# Force_sensor_PCB_Easy_EDA_Proffesional_p.net
KiCad netlist of a schematic drawn in EasyEDA Pro
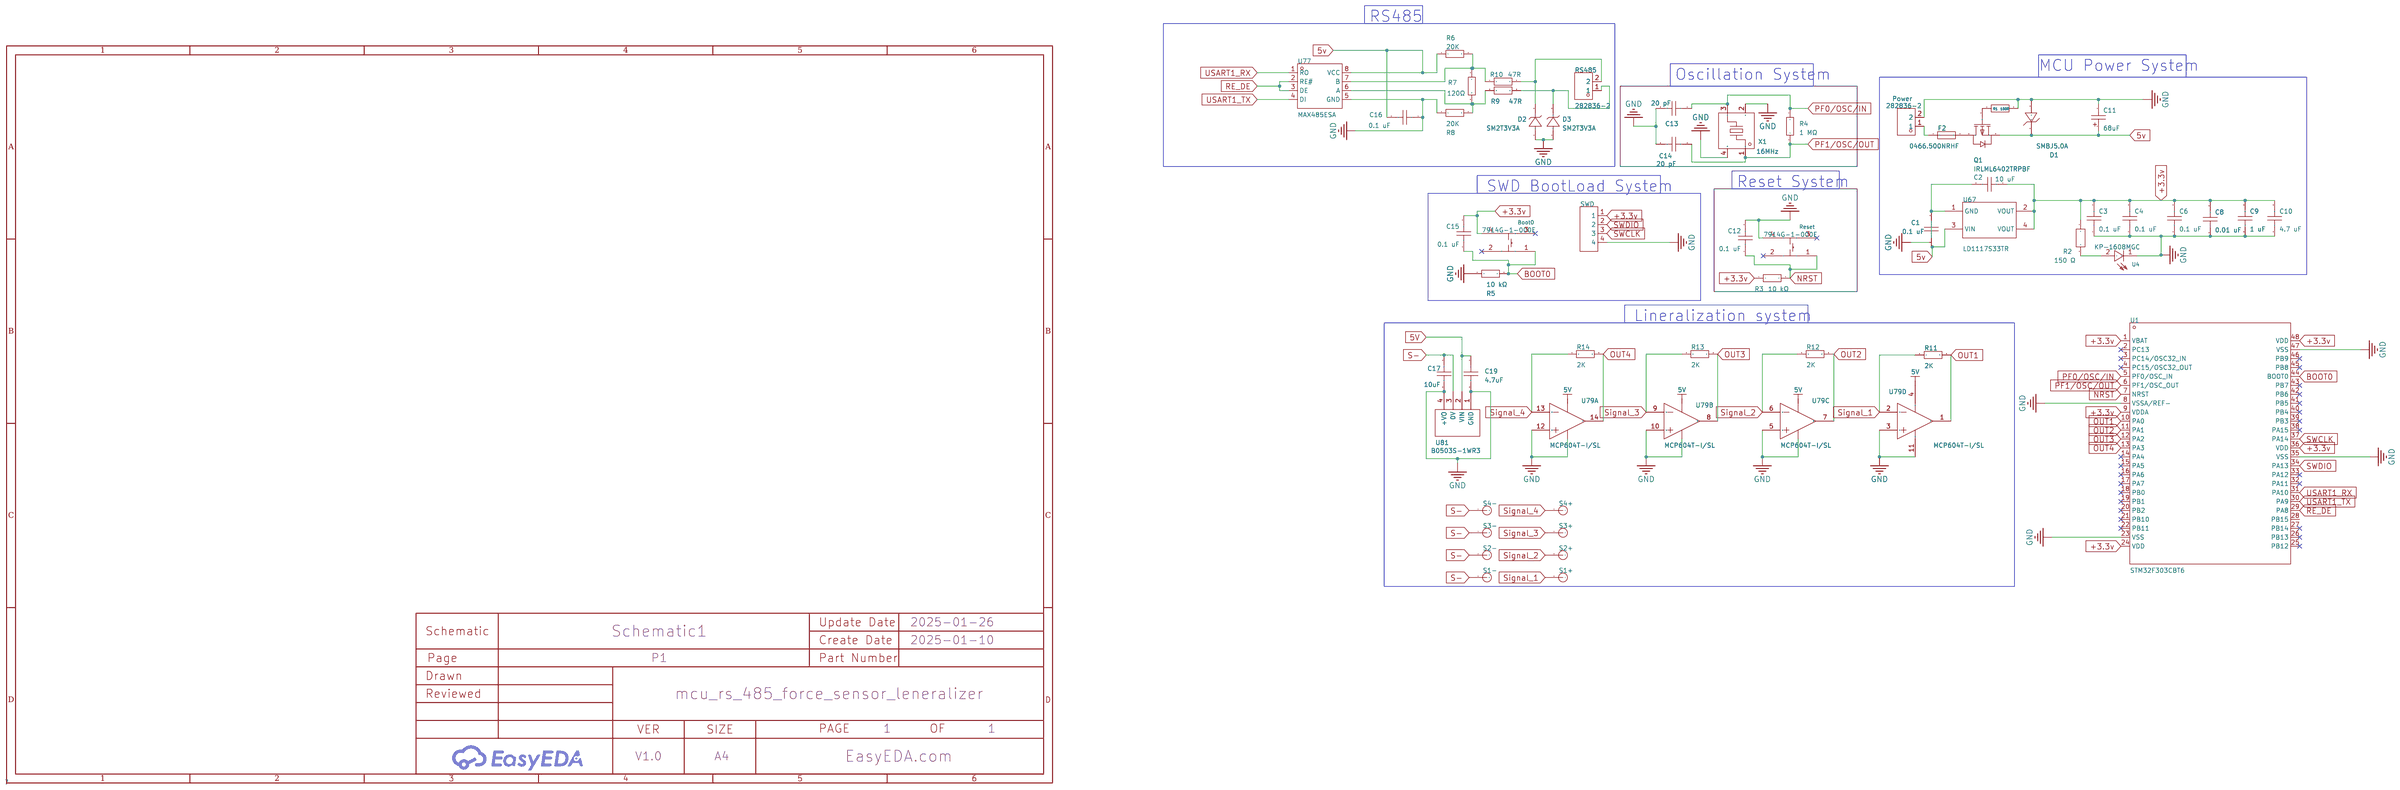
[diagram p0: schematic sheet]

(export (version "E")
  (design (tool "Eeschema 10.0.6"))
  (components
    (comp (ref "Boot0")
      (value "7914G-1-000E")
      (footprint "easyedapro:KEY-SMD_4P-L5.0-W5.0-P2.54-LS5.5-BL")
      (fields (field (name "Manufacturer") "BOURNS"))
      (libsource (lib "easyedapro") (part "7914G-1-000E"))
    )
    (comp (ref "C1")
      (value "0.1 uF")
      (footprint "easyedapro:C0201")
      (libsource (lib "easyedapro") (part "CAP"))
    )
    (comp (ref "C2")
      (value "10 uF")
      (footprint "easyedapro:C0201")
      (libsource (lib "easyedapro") (part "CAP"))
    )
    (comp (ref "C3")
      (value "0.1 uF")
      (footprint "easyedapro:C0201")
      (libsource (lib "easyedapro") (part "CAP"))
    )
    (comp (ref "C4")
      (value "0.1 uF")
      (footprint "easyedapro:C0201")
      (libsource (lib "easyedapro") (part "CAP"))
    )
    (comp (ref "C6")
      (value "0.1 uF")
      (footprint "easyedapro:C0201")
      (libsource (lib "easyedapro") (part "CAP"))
    )
    (comp (ref "C8")
      (value "0.01 uF")
      (footprint "easyedapro:C0201")
      (libsource (lib "easyedapro") (part "CAP"))
    )
    (comp (ref "C9")
      (value "1 uF")
      (footprint "easyedapro:C0201")
      (libsource (lib "easyedapro") (part "CAP"))
    )
    (comp (ref "C10")
      (value "4.7 uF")
      (footprint "easyedapro:C0201")
      (libsource (lib "easyedapro") (part "CAP"))
    )
    (comp (ref "C11")
      (value "68uF")
      (footprint "easyedapro:CASE-B_3528")
      (fields
        (field (name "Manufacturer Part") "TLJB227M006R0500")
        (field (name "Manufacturer") "Kyocera AVX")
      )
      (libsource (lib "easyedapro") (part "TLJB227M006R0500"))
    )
    (comp (ref "C12")
      (value "0.1 uF")
      (footprint "easyedapro:C0201")
      (libsource (lib "easyedapro") (part "CAP"))
    )
    (comp (ref "C13")
      (value "20 pF")
      (footprint "easyedapro:C0201")
      (libsource (lib "easyedapro") (part "CAP"))
    )
    (comp (ref "C14")
      (value "20 pF")
      (footprint "easyedapro:C0201")
      (libsource (lib "easyedapro") (part "CAP"))
    )
    (comp (ref "C15")
      (value "0.1 uF")
      (footprint "easyedapro:C0201")
      (libsource (lib "easyedapro") (part "CAP"))
    )
    (comp (ref "C16")
      (value "0.1 uF")
      (footprint "easyedapro:C0201")
      (libsource (lib "easyedapro") (part "CAP"))
    )
    (comp (ref "C17")
      (value "10uF")
      (footprint "easyedapro:C0201")
      (libsource (lib "easyedapro") (part "CAP"))
    )
    (comp (ref "C19")
      (value "4.7uF")
      (footprint "easyedapro:C0201")
      (libsource (lib "easyedapro") (part "CAP"))
    )
    (comp (ref "D1")
      (value "SMBJ5.0A")
      (footprint "easyedapro:SMB_L4.3-W3.6-LS5.4-RD")
      (fields (field (name "Manufacturer") "SEMBO(深波)"))
      (libsource (lib "easyedapro") (part "SMBJ5.0A_C782420"))
    )
    (comp (ref "D2")
      (value "SM2T3V3A")
      (footprint "easyedapro:DO-216AA_L1.9-W1.9-LS3.8-FD")
      (fields (field (name "Manufacturer") "ST(意法半导体)"))
      (libsource (lib "easyedapro") (part "SM2T3V3A"))
    )
    (comp (ref "D3")
      (value "SM2T3V3A")
      (footprint "easyedapro:DO-216AA_L1.9-W1.9-LS3.8-FD")
      (fields (field (name "Manufacturer") "ST(意法半导体)"))
      (libsource (lib "easyedapro") (part "SM2T3V3A"))
    )
    (comp (ref "F2")
      (value "0466.500NRHF")
      (footprint "easyedapro:F1206")
      (fields (field (name "Manufacturer") "Littelfuse(美国力特)"))
      (libsource (lib "easyedapro") (part "0466.500NRHF"))
    )
    (comp (ref "Power")
      (value "282836-2")
      (footprint "easyedapro:CONN-TH_2P-P5.00_282836-2")
      (fields (field (name "Manufacturer") "TE Connectivity(泰科电子)"))
      (libsource (lib "easyedapro") (part "282836-2"))
    )
    (comp (ref "Q1")
      (value "IRLML6402TRPBF")
      (footprint "easyedapro:SOT-23-3_L2.9-W1.6-P1.90-LS2.8-BR")
      (fields (field (name "Manufacturer") "Infineon(英飞凌)"))
      (libsource (lib "easyedapro") (part "IRLML6402TRPBF"))
    )
    (comp (ref "R1")
      (value "100R")
      (footprint "easyedapro:R0603")
      (libsource (lib "easyedapro") (part "Res"))
    )
    (comp (ref "R2")
      (value "150 Ω")
      (footprint "easyedapro:R0805")
      (fields (field (name "Manufacturer Part") "ERJ6ENF2053V") (field (name "Manufacturer") "PANASONIC(松下)"))
      (libsource (lib "easyedapro") (part "ERJ6ENF2053V"))
    )
    (comp (ref "R3")
      (value "10 kΩ")
      (footprint "easyedapro:R0603")
      (libsource (lib "easyedapro") (part "Res"))
    )
    (comp (ref "R4")
      (value "1 MΩ")
      (footprint "easyedapro:R0603")
      (libsource (lib "easyedapro") (part "Res"))
    )
    (comp (ref "R5")
      (value "10 kΩ")
      (footprint "easyedapro:R0603")
      (libsource (lib "easyedapro") (part "Res"))
    )
    (comp (ref "R6") (value "20K") (footprint "easyedapro:R0603") (libsource (lib "easyedapro") (part "Res")))
    (comp (ref "R7")
      (value "120Ω")
      (footprint "easyedapro:R1206")
      (fields
        (field (name "Manufacturer Part") "1206W4J0121T5E")
        (field (name "Manufacturer") "UNI-ROYAL(厚声)")
      )
      (libsource (lib "easyedapro") (part "1206W4J0121T5E"))
    )
    (comp (ref "R8") (value "20K") (footprint "easyedapro:R0603") (libsource (lib "easyedapro") (part "Res")))
    (comp (ref "R9") (value "47R") (footprint "easyedapro:R0603") (libsource (lib "easyedapro") (part "Res")))
    (comp (ref "R10")
      (value "47R")
      (footprint "easyedapro:R0603")
      (libsource (lib "easyedapro") (part "Res"))
    )
    (comp (ref "R11") (value "2K") (footprint "easyedapro:R0603") (libsource (lib "easyedapro") (part "Res")))
    (comp (ref "R12") (value "2K") (footprint "easyedapro:R0603") (libsource (lib "easyedapro") (part "Res")))
    (comp (ref "R13") (value "2K") (footprint "easyedapro:R0603") (libsource (lib "easyedapro") (part "Res")))
    (comp (ref "R14") (value "2K") (footprint "easyedapro:R0603") (libsource (lib "easyedapro") (part "Res")))
    (comp (ref "Reset")
      (value "7914G-1-000E")
      (footprint "easyedapro:KEY-SMD_4P-L5.0-W5.0-P2.54-LS5.5-BL")
      (fields (field (name "Manufacturer") "BOURNS"))
      (libsource (lib "easyedapro") (part "7914G-1-000E"))
    )
    (comp (ref "RS485")
      (value "282836-2")
      (footprint "easyedapro:CONN-TH_2P-P5.00_282836-2")
      (fields (field (name "Manufacturer") "TE Connectivity(泰科电子)"))
      (libsource (lib "easyedapro") (part "282836-2"))
    )
    (comp (ref "S1+")
      (value "~")
      (footprint "easyedapro:robust_pin")
      (libsource (lib "easyedapro") (part "robust_pin"))
    )
    (comp (ref "S1-")
      (value "~")
      (footprint "easyedapro:robust_pin")
      (libsource (lib "easyedapro") (part "robust_pin"))
    )
    (comp (ref "S2+")
      (value "~")
      (footprint "easyedapro:robust_pin")
      (libsource (lib "easyedapro") (part "robust_pin"))
    )
    (comp (ref "S2-")
      (value "~")
      (footprint "easyedapro:robust_pin")
      (libsource (lib "easyedapro") (part "robust_pin"))
    )
    (comp (ref "S3+")
      (value "~")
      (footprint "easyedapro:robust_pin")
      (libsource (lib "easyedapro") (part "robust_pin"))
    )
    (comp (ref "S3-")
      (value "~")
      (footprint "easyedapro:robust_pin")
      (libsource (lib "easyedapro") (part "robust_pin"))
    )
    (comp (ref "S4+")
      (value "~")
      (footprint "easyedapro:robust_pin")
      (libsource (lib "easyedapro") (part "robust_pin"))
    )
    (comp (ref "S4-")
      (value "~")
      (footprint "easyedapro:robust_pin")
      (libsource (lib "easyedapro") (part "robust_pin"))
    )
    (comp (ref "SWD")
      (value "~")
      (footprint "easyedapro:HDR-TH_4P-P2.54-V-M")
      (libsource (lib "easyedapro") (part "PZ254V-11-04P"))
    )
    (comp (ref "U1")
      (value "STM32F303CBT6")
      (footprint "easyedapro:LQFP-48_L7.0-W7.0-P0.50-LS9.0-BL")
      (fields (field (name "Manufacturer") "ST(意法半导体)"))
      (libsource (lib "easyedapro") (part "STM32F303CBT6"))
    )
    (comp (ref "U4")
      (value "KP-1608MGC")
      (footprint "easyedapro:LED0603-RD_GREEN")
      (fields (field (name "Manufacturer") "Kingbright"))
      (libsource (lib "easyedapro") (part "KP-1608MGC"))
    )
    (comp (ref "U67")
      (value "LD1117S33TR")
      (footprint "easyedapro:SOT-223_L6.5-W3.5-P2.30-LS7.0-BR")
      (fields (field (name "Manufacturer") "ST(意法半导体)"))
      (libsource (lib "easyedapro") (part "LD1117S33TR"))
    )
    (comp (ref "U77")
      (value "MAX485ESA")
      (footprint "easyedapro:SOIC-8_L4.9-W3.9-P1.27-LS6.0-BL")
      (fields (field (name "Manufacturer") "TWGMC(台湾迪嘉)"))
      (libsource (lib "easyedapro") (part "MAX485ESA_C5279041"))
    )
    (comp (ref "U79")
      (value "MCP604T-I/SL")
      (footprint "easyedapro:SOIC-14_L8.7-W3.9-P1.27-LS6.0-BL")
      (fields (field (name "Manufacturer") "MICROCHIP(美国微芯)"))
      (libsource (lib "easyedapro") (part "MCP604T-I/SL"))
    )
    (comp (ref "U81")
      (value "B0503S-1WR3")
      (footprint "easyedapro:PWRM-TH_B0503S-1WR2")
      (fields (field (name "Manufacturer") "DEXU(德旭电子)"))
      (libsource (lib "easyedapro") (part "B0503S-1WR3_C909801"))
    )
    (comp (ref "X1")
      (value "16MHz")
      (footprint "easyedapro:CRYSTAL-SMD_4P-L5.0-W3.2-BL")
      (fields
        (field (name "Manufacturer Part") "HY13MSMD50324POB1R10")
        (field (name "Manufacturer") "Huiyuan crystal(惠源晶工)")
      )
      (libsource (lib "easyedapro") (part "HY13MSMD50324POB1R10"))
    )
  )
  (nets
    (net (code "1") (name "+3.3v") (class "Default")
      (node (ref "Boot0") (pin "4") (pinfunction "4_4") (pintype "unspecified"))
      (node (ref "C10") (pin "2") (pinfunction "2_2") (pintype "input"))
      (node (ref "C15") (pin "2") (pinfunction "2_2") (pintype "input"))
      (node (ref "C2") (pin "1") (pinfunction "1_1") (pintype "input"))
      (node (ref "C3") (pin "2") (pinfunction "2_2") (pintype "input"))
      (node (ref "C4") (pin "2") (pinfunction "2_2") (pintype "input"))
      (node (ref "C6") (pin "2") (pinfunction "2_2") (pintype "input"))
      (node (ref "C8") (pin "2") (pinfunction "2_2") (pintype "input"))
      (node (ref "C9") (pin "2") (pinfunction "2_2") (pintype "input"))
      (node (ref "R2") (pin "1") (pinfunction "1_1") (pintype "unspecified"))
      (node (ref "R3") (pin "1") (pinfunction "1_1") (pintype "input"))
      (node (ref "SWD") (pin "1") (pinfunction "1_1") (pintype "unspecified"))
      (node (ref "U1") (pin "1") (pinfunction "VBAT_1") (pintype "unspecified"))
      (node (ref "U1") (pin "24") (pinfunction "VDD_24") (pintype "unspecified"))
      (node (ref "U1") (pin "36") (pinfunction "VDD_36") (pintype "unspecified"))
      (node (ref "U1") (pin "48") (pinfunction "VDD_48") (pintype "unspecified"))
      (node (ref "U1") (pin "9") (pinfunction "VDDA_9") (pintype "unspecified"))
      (node (ref "U67") (pin "2") (pinfunction "VOUT_2") (pintype "unspecified"))
      (node (ref "U67") (pin "4") (pinfunction "VOUT_4") (pintype "unspecified"))
    )
    (net (code "2") (name "5V") (class "Default")
      (node (ref "C19") (pin "1") (pinfunction "1_1") (pintype "input"))
      (node (ref "U79") (pin "4") (pinfunction "VDD_4") (pintype "unspecified"))
      (node (ref "U81") (pin "2") (pinfunction "VIN_2") (pintype "unspecified"))
    )
    (net (code "3") (name "5v") (class "Default")
      (node (ref "C1") (pin "1") (pinfunction "1_1") (pintype "input"))
      (node (ref "C11") (pin "1") (pinfunction "1_1") (pintype "input"))
      (node (ref "C16") (pin "2") (pinfunction "2_2") (pintype "input"))
      (node (ref "D1") (pin "1") (pinfunction "C_1") (pintype "unspecified"))
      (node (ref "Q1") (pin "2") (pinfunction "S_2") (pintype "unspecified"))
      (node (ref "R6") (pin "1") (pinfunction "1_1") (pintype "input"))
      (node (ref "U67") (pin "3") (pinfunction "VIN_3") (pintype "unspecified"))
      (node (ref "U77") (pin "8") (pinfunction "VCC_8") (pintype "unspecified"))
    )
    (net (code "4") (name "BOOT0") (class "Default")
      (node (ref "Boot0") (pin "1") (pinfunction "1_1") (pintype "unspecified"))
      (node (ref "C15") (pin "1") (pinfunction "1_1") (pintype "input"))
      (node (ref "R5") (pin "2") (pinfunction "2_2") (pintype "input"))
      (node (ref "U1") (pin "44") (pinfunction "BOOT0_44") (pintype "unspecified"))
    )
    (net (code "5") (name "GND") (class "Default")
      (node (ref "C1") (pin "2") (pinfunction "2_2") (pintype "input"))
      (node (ref "C10") (pin "1") (pinfunction "1_1") (pintype "input"))
      (node (ref "C11") (pin "2") (pinfunction "2_2") (pintype "input"))
      (node (ref "C12") (pin "2") (pinfunction "2_2") (pintype "input"))
      (node (ref "C13") (pin "2") (pinfunction "2_2") (pintype "input"))
      (node (ref "C14") (pin "2") (pinfunction "2_2") (pintype "input"))
      (node (ref "C16") (pin "1") (pinfunction "1_1") (pintype "input"))
      (node (ref "C17") (pin "2") (pinfunction "2_2") (pintype "input"))
      (node (ref "C19") (pin "2") (pinfunction "2_2") (pintype "input"))
      (node (ref "C2") (pin "2") (pinfunction "2_2") (pintype "input"))
      (node (ref "C3") (pin "1") (pinfunction "1_1") (pintype "input"))
      (node (ref "C4") (pin "1") (pinfunction "1_1") (pintype "input"))
      (node (ref "C6") (pin "1") (pinfunction "1_1") (pintype "input"))
      (node (ref "C8") (pin "1") (pinfunction "1_1") (pintype "input"))
      (node (ref "C9") (pin "1") (pinfunction "1_1") (pintype "input"))
      (node (ref "D1") (pin "2") (pinfunction "A_2") (pintype "unspecified"))
      (node (ref "D2") (pin "1") (pinfunction "A_1") (pintype "unspecified"))
      (node (ref "D3") (pin "1") (pinfunction "A_1") (pintype "unspecified"))
      (node (ref "Power") (pin "2") (pinfunction "2_2") (pintype "unspecified"))
      (node (ref "R1") (pin "2") (pinfunction "2_2") (pintype "input"))
      (node (ref "R5") (pin "1") (pinfunction "1_1") (pintype "input"))
      (node (ref "R8") (pin "1") (pinfunction "1_1") (pintype "input"))
      (node (ref "Reset") (pin "4") (pinfunction "4_4") (pintype "unspecified"))
      (node (ref "SWD") (pin "4") (pinfunction "4_4") (pintype "unspecified"))
      (node (ref "U1") (pin "23") (pinfunction "VSS_23") (pintype "unspecified"))
      (node (ref "U1") (pin "35") (pinfunction "VSS_35") (pintype "unspecified"))
      (node (ref "U1") (pin "47") (pinfunction "VSS_47") (pintype "unspecified"))
      (node (ref "U1") (pin "8") (pinfunction "VSSA/REF-_8") (pintype "unspecified"))
      (node (ref "U4") (pin "1") (pinfunction "C_1") (pintype "input"))
      (node (ref "U67") (pin "1") (pinfunction "GND_1") (pintype "unspecified"))
      (node (ref "U77") (pin "5") (pinfunction "GND_5") (pintype "unspecified"))
      (node (ref "U79") (pin "10") (pinfunction "VINC+_10") (pintype "unspecified"))
      (node (ref "U79") (pin "11") (pinfunction "VSS_11") (pintype "unspecified"))
      (node (ref "U79") (pin "12") (pinfunction "VIND+_12") (pintype "unspecified"))
      (node (ref "U79") (pin "3") (pinfunction "VINA+_3") (pintype "unspecified"))
      (node (ref "U79") (pin "5") (pinfunction "VINB+_5") (pintype "unspecified"))
      (node (ref "U81") (pin "1") (pinfunction "GND_1") (pintype "unspecified"))
      (node (ref "U81") (pin "4") (pinfunction "+VO_4") (pintype "unspecified"))
      (node (ref "X1") (pin "2") (pinfunction "GND_2") (pintype "input"))
      (node (ref "X1") (pin "4") (pinfunction "GND_4") (pintype "input"))
    )
    (net (code "6") (name "NRST") (class "Default")
      (node (ref "C12") (pin "1") (pinfunction "1_1") (pintype "input"))
      (node (ref "R3") (pin "2") (pinfunction "2_2") (pintype "input"))
      (node (ref "Reset") (pin "1") (pinfunction "1_1") (pintype "unspecified"))
      (node (ref "U1") (pin "7") (pinfunction "NRST_7") (pintype "unspecified"))
    )
    (net (code "7") (name "Net-(D2-K)") (class "Default")
      (node (ref "D2") (pin "2") (pinfunction "K_2") (pintype "unspecified"))
      (node (ref "R10") (pin "2") (pinfunction "2_2") (pintype "input"))
      (node (ref "RS485") (pin "2") (pinfunction "2_2") (pintype "unspecified"))
    )
    (net (code "8") (name "Net-(D3-K)") (class "Default")
      (node (ref "D3") (pin "2") (pinfunction "K_2") (pintype "unspecified"))
      (node (ref "R9") (pin "2") (pinfunction "2_2") (pintype "input"))
      (node (ref "RS485") (pin "1") (pinfunction "1_1") (pintype "unspecified"))
    )
    (net (code "9") (name "Net-(F2-Pad1)") (class "Default")
      (node (ref "F2") (pin "1") (pinfunction "1_1") (pintype "unspecified"))
      (node (ref "Power") (pin "1") (pinfunction "1_1") (pintype "unspecified"))
    )
    (net (code "10") (name "Net-(Q1-D)") (class "Default")
      (node (ref "F2") (pin "2") (pinfunction "2_2") (pintype "unspecified"))
      (node (ref "Q1") (pin "3") (pinfunction "D_3") (pintype "unspecified"))
    )
    (net (code "11") (name "Net-(Q1-G)") (class "Default")
      (node (ref "Q1") (pin "1") (pinfunction "G_1") (pintype "unspecified"))
      (node (ref "R1") (pin "1") (pinfunction "1_1") (pintype "input"))
    )
    (net (code "12") (name "Net-(U4-A)") (class "Default")
      (node (ref "R2") (pin "2") (pinfunction "2_2") (pintype "unspecified"))
      (node (ref "U4") (pin "2") (pinfunction "A_2") (pintype "input"))
    )
    (net (code "13") (name "Net-(U77-A)") (class "Default")
      (node (ref "R7") (pin "2") (pinfunction "2_2") (pintype "input"))
      (node (ref "R8") (pin "2") (pinfunction "2_2") (pintype "input"))
      (node (ref "R9") (pin "1") (pinfunction "1_1") (pintype "input"))
      (node (ref "U77") (pin "6") (pinfunction "A_6") (pintype "unspecified"))
    )
    (net (code "14") (name "Net-(U77-B)") (class "Default")
      (node (ref "R10") (pin "1") (pinfunction "1_1") (pintype "input"))
      (node (ref "R6") (pin "2") (pinfunction "2_2") (pintype "input"))
      (node (ref "R7") (pin "1") (pinfunction "1_1") (pintype "input"))
      (node (ref "U77") (pin "7") (pinfunction "B_7") (pintype "unspecified"))
    )
    (net (code "15") (name "OUT1") (class "Default")
      (node (ref "R11") (pin "2") (pinfunction "2_2") (pintype "input"))
      (node (ref "U1") (pin "10") (pinfunction "PA0_10") (pintype "unspecified"))
      (node (ref "U79") (pin "1") (pinfunction "VOUTA_1") (pintype "output"))
    )
    (net (code "16") (name "OUT2") (class "Default")
      (node (ref "R12") (pin "2") (pinfunction "2_2") (pintype "input"))
      (node (ref "U1") (pin "11") (pinfunction "PA1_11") (pintype "unspecified"))
      (node (ref "U79") (pin "7") (pinfunction "VOUTB_7") (pintype "output"))
    )
    (net (code "17") (name "OUT3") (class "Default")
      (node (ref "R13") (pin "2") (pinfunction "2_2") (pintype "input"))
      (node (ref "U1") (pin "12") (pinfunction "PA2_12") (pintype "unspecified"))
      (node (ref "U79") (pin "8") (pinfunction "VOUTC_8") (pintype "output"))
    )
    (net (code "18") (name "OUT4") (class "Default")
      (node (ref "R14") (pin "2") (pinfunction "2_2") (pintype "input"))
      (node (ref "U1") (pin "13") (pinfunction "PA3_13") (pintype "unspecified"))
      (node (ref "U79") (pin "14") (pinfunction "VOUTD_14") (pintype "output"))
    )
    (net (code "19") (name "PF0{slash}OSC{slash}IN") (class "Default")
      (node (ref "C13") (pin "1") (pinfunction "1_1") (pintype "input"))
      (node (ref "R4") (pin "1") (pinfunction "1_1") (pintype "input"))
      (node (ref "U1") (pin "5") (pinfunction "PF0/OSC_IN_5") (pintype "unspecified"))
      (node (ref "X1") (pin "3") (pinfunction "3_3") (pintype "input"))
    )
    (net (code "20") (name "PF1{slash}OSC{slash}OUT") (class "Default")
      (node (ref "C14") (pin "1") (pinfunction "1_1") (pintype "input"))
      (node (ref "R4") (pin "2") (pinfunction "2_2") (pintype "input"))
      (node (ref "U1") (pin "6") (pinfunction "PF1/OSC_OUT_6") (pintype "unspecified"))
      (node (ref "X1") (pin "1") (pinfunction "1_1") (pintype "input"))
    )
    (net (code "21") (name "RE_DE") (class "Default")
      (node (ref "U1") (pin "29") (pinfunction "PA8_29") (pintype "unspecified"))
      (node (ref "U77") (pin "2") (pinfunction "RE#_2") (pintype "unspecified"))
      (node (ref "U77") (pin "3") (pinfunction "DE_3") (pintype "unspecified"))
    )
    (net (code "22") (name "S-") (class "Default")
      (node (ref "C17") (pin "1") (pinfunction "1_1") (pintype "input"))
      (node (ref "S1-") (pin "1") (pinfunction "1_1") (pintype "input"))
      (node (ref "S2-") (pin "1") (pinfunction "1_1") (pintype "input"))
      (node (ref "S3-") (pin "1") (pinfunction "1_1") (pintype "input"))
      (node (ref "S4-") (pin "1") (pinfunction "1_1") (pintype "input"))
      (node (ref "U81") (pin "3") (pinfunction "0V_3") (pintype "unspecified"))
    )
    (net (code "23") (name "SWCLK") (class "Default")
      (node (ref "SWD") (pin "3") (pinfunction "3_3") (pintype "unspecified"))
      (node (ref "U1") (pin "37") (pinfunction "PA14_37") (pintype "unspecified"))
    )
    (net (code "24") (name "SWDIO") (class "Default")
      (node (ref "SWD") (pin "2") (pinfunction "2_2") (pintype "unspecified"))
      (node (ref "U1") (pin "34") (pinfunction "PA13_34") (pintype "unspecified"))
    )
    (net (code "25") (name "Signal_1") (class "Default")
      (node (ref "R11") (pin "1") (pinfunction "1_1") (pintype "input"))
      (node (ref "S1+") (pin "1") (pinfunction "1_1") (pintype "input"))
      (node (ref "U79") (pin "2") (pinfunction "VINA-_2") (pintype "unspecified"))
    )
    (net (code "26") (name "Signal_2") (class "Default")
      (node (ref "R12") (pin "1") (pinfunction "1_1") (pintype "input"))
      (node (ref "S2+") (pin "1") (pinfunction "1_1") (pintype "input"))
      (node (ref "U79") (pin "6") (pinfunction "VINB-_6") (pintype "unspecified"))
    )
    (net (code "27") (name "Signal_3") (class "Default")
      (node (ref "R13") (pin "1") (pinfunction "1_1") (pintype "input"))
      (node (ref "S3+") (pin "1") (pinfunction "1_1") (pintype "input"))
      (node (ref "U79") (pin "9") (pinfunction "VINC-_9") (pintype "unspecified"))
    )
    (net (code "28") (name "Signal_4") (class "Default")
      (node (ref "R14") (pin "1") (pinfunction "1_1") (pintype "input"))
      (node (ref "S4+") (pin "1") (pinfunction "1_1") (pintype "input"))
      (node (ref "U79") (pin "13") (pinfunction "VIND-_13") (pintype "unspecified"))
    )
    (net (code "29") (name "USART1_RX") (class "Default")
      (node (ref "U1") (pin "31") (pinfunction "PA10_31") (pintype "unspecified"))
      (node (ref "U77") (pin "1") (pinfunction "RO_1") (pintype "unspecified"))
    )
    (net (code "30") (name "USART1_TX") (class "Default")
      (node (ref "U1") (pin "30") (pinfunction "PA9_30") (pintype "unspecified"))
      (node (ref "U77") (pin "4") (pinfunction "DI_4") (pintype "unspecified"))
    )
    (net (code "31") (name "unconnected-(Boot0-Pad2)") (class "Default")
      (node (ref "Boot0") (pin "2") (pinfunction "2_2") (pintype "unspecified+no_connect"))
    )
    (net (code "32") (name "unconnected-(Boot0-Pad3)") (class "Default")
      (node (ref "Boot0") (pin "3") (pinfunction "3_3") (pintype "unspecified+no_connect"))
    )
    (net (code "33") (name "unconnected-(Reset-Pad2)") (class "Default")
      (node (ref "Reset") (pin "2") (pinfunction "2_2") (pintype "unspecified+no_connect"))
    )
    (net (code "34") (name "unconnected-(Reset-Pad3)") (class "Default")
      (node (ref "Reset") (pin "3") (pinfunction "3_3") (pintype "unspecified+no_connect"))
    )
    (net (code "35") (name "unconnected-(U1-PA4-Pad14)") (class "Default")
      (node (ref "U1") (pin "14") (pinfunction "PA4_14") (pintype "unspecified+no_connect"))
    )
    (net (code "36") (name "unconnected-(U1-PA5-Pad15)") (class "Default")
      (node (ref "U1") (pin "15") (pinfunction "PA5_15") (pintype "unspecified+no_connect"))
    )
    (net (code "37") (name "unconnected-(U1-PA6-Pad16)") (class "Default")
      (node (ref "U1") (pin "16") (pinfunction "PA6_16") (pintype "unspecified+no_connect"))
    )
    (net (code "38") (name "unconnected-(U1-PA7-Pad17)") (class "Default")
      (node (ref "U1") (pin "17") (pinfunction "PA7_17") (pintype "unspecified+no_connect"))
    )
    (net (code "39") (name "unconnected-(U1-PA11-Pad32)") (class "Default")
      (node (ref "U1") (pin "32") (pinfunction "PA11_32") (pintype "unspecified+no_connect"))
    )
    (net (code "40") (name "unconnected-(U1-PA12-Pad33)") (class "Default")
      (node (ref "U1") (pin "33") (pinfunction "PA12_33") (pintype "unspecified+no_connect"))
    )
    (net (code "41") (name "unconnected-(U1-PA15-Pad38)") (class "Default")
      (node (ref "U1") (pin "38") (pinfunction "PA15_38") (pintype "unspecified+no_connect"))
    )
    (net (code "42") (name "unconnected-(U1-PB0-Pad18)") (class "Default")
      (node (ref "U1") (pin "18") (pinfunction "PB0_18") (pintype "unspecified+no_connect"))
    )
    (net (code "43") (name "unconnected-(U1-PB1-Pad19)") (class "Default")
      (node (ref "U1") (pin "19") (pinfunction "PB1_19") (pintype "unspecified+no_connect"))
    )
    (net (code "44") (name "unconnected-(U1-PB2-Pad20)") (class "Default")
      (node (ref "U1") (pin "20") (pinfunction "PB2_20") (pintype "unspecified+no_connect"))
    )
    (net (code "45") (name "unconnected-(U1-PB3-Pad39)") (class "Default")
      (node (ref "U1") (pin "39") (pinfunction "PB3_39") (pintype "unspecified+no_connect"))
    )
    (net (code "46") (name "unconnected-(U1-PB4-Pad40)") (class "Default")
      (node (ref "U1") (pin "40") (pinfunction "PB4_40") (pintype "unspecified+no_connect"))
    )
    (net (code "47") (name "unconnected-(U1-PB5-Pad41)") (class "Default")
      (node (ref "U1") (pin "41") (pinfunction "PB5_41") (pintype "unspecified+no_connect"))
    )
    (net (code "48") (name "unconnected-(U1-PB6-Pad42)") (class "Default")
      (node (ref "U1") (pin "42") (pinfunction "PB6_42") (pintype "unspecified+no_connect"))
    )
    (net (code "49") (name "unconnected-(U1-PB7-Pad43)") (class "Default")
      (node (ref "U1") (pin "43") (pinfunction "PB7_43") (pintype "unspecified+no_connect"))
    )
    (net (code "50") (name "unconnected-(U1-PB8-Pad45)") (class "Default")
      (node (ref "U1") (pin "45") (pinfunction "PB8_45") (pintype "unspecified+no_connect"))
    )
    (net (code "51") (name "unconnected-(U1-PB9-Pad46)") (class "Default")
      (node (ref "U1") (pin "46") (pinfunction "PB9_46") (pintype "unspecified+no_connect"))
    )
    (net (code "52") (name "unconnected-(U1-PB10-Pad21)") (class "Default")
      (node (ref "U1") (pin "21") (pinfunction "PB10_21") (pintype "unspecified+no_connect"))
    )
    (net (code "53") (name "unconnected-(U1-PB11-Pad22)") (class "Default")
      (node (ref "U1") (pin "22") (pinfunction "PB11_22") (pintype "unspecified+no_connect"))
    )
    (net (code "54") (name "unconnected-(U1-PB12-Pad25)") (class "Default")
      (node (ref "U1") (pin "25") (pinfunction "PB12_25") (pintype "unspecified+no_connect"))
    )
    (net (code "55") (name "unconnected-(U1-PB13-Pad26)") (class "Default")
      (node (ref "U1") (pin "26") (pinfunction "PB13_26") (pintype "unspecified+no_connect"))
    )
    (net (code "56") (name "unconnected-(U1-PB14-Pad27)") (class "Default")
      (node (ref "U1") (pin "27") (pinfunction "PB14_27") (pintype "unspecified+no_connect"))
    )
    (net (code "57") (name "unconnected-(U1-PB15-Pad28)") (class "Default")
      (node (ref "U1") (pin "28") (pinfunction "PB15_28") (pintype "unspecified"))
    )
    (net (code "58") (name "unconnected-(U1-PC13-Pad2)") (class "Default")
      (node (ref "U1") (pin "2") (pinfunction "PC13_2") (pintype "unspecified+no_connect"))
    )
    (net (code "59") (name "unconnected-(U1-PC14{slash}OSC32_IN-Pad3)") (class "Default")
      (node (ref "U1") (pin "3") (pinfunction "PC14/OSC32_IN_3") (pintype "unspecified+no_connect"))
    )
    (net (code "60") (name "unconnected-(U1-PC15{slash}OSC32_OUT-Pad4)") (class "Default")
      (node (ref "U1") (pin "4") (pinfunction "PC15/OSC32_OUT_4") (pintype "unspecified+no_connect"))
    )
  )
)
